# BLE112_Breakout_Board_v2_1_8mil.net
KiCad netlist of a schematic drawn in EAGLE
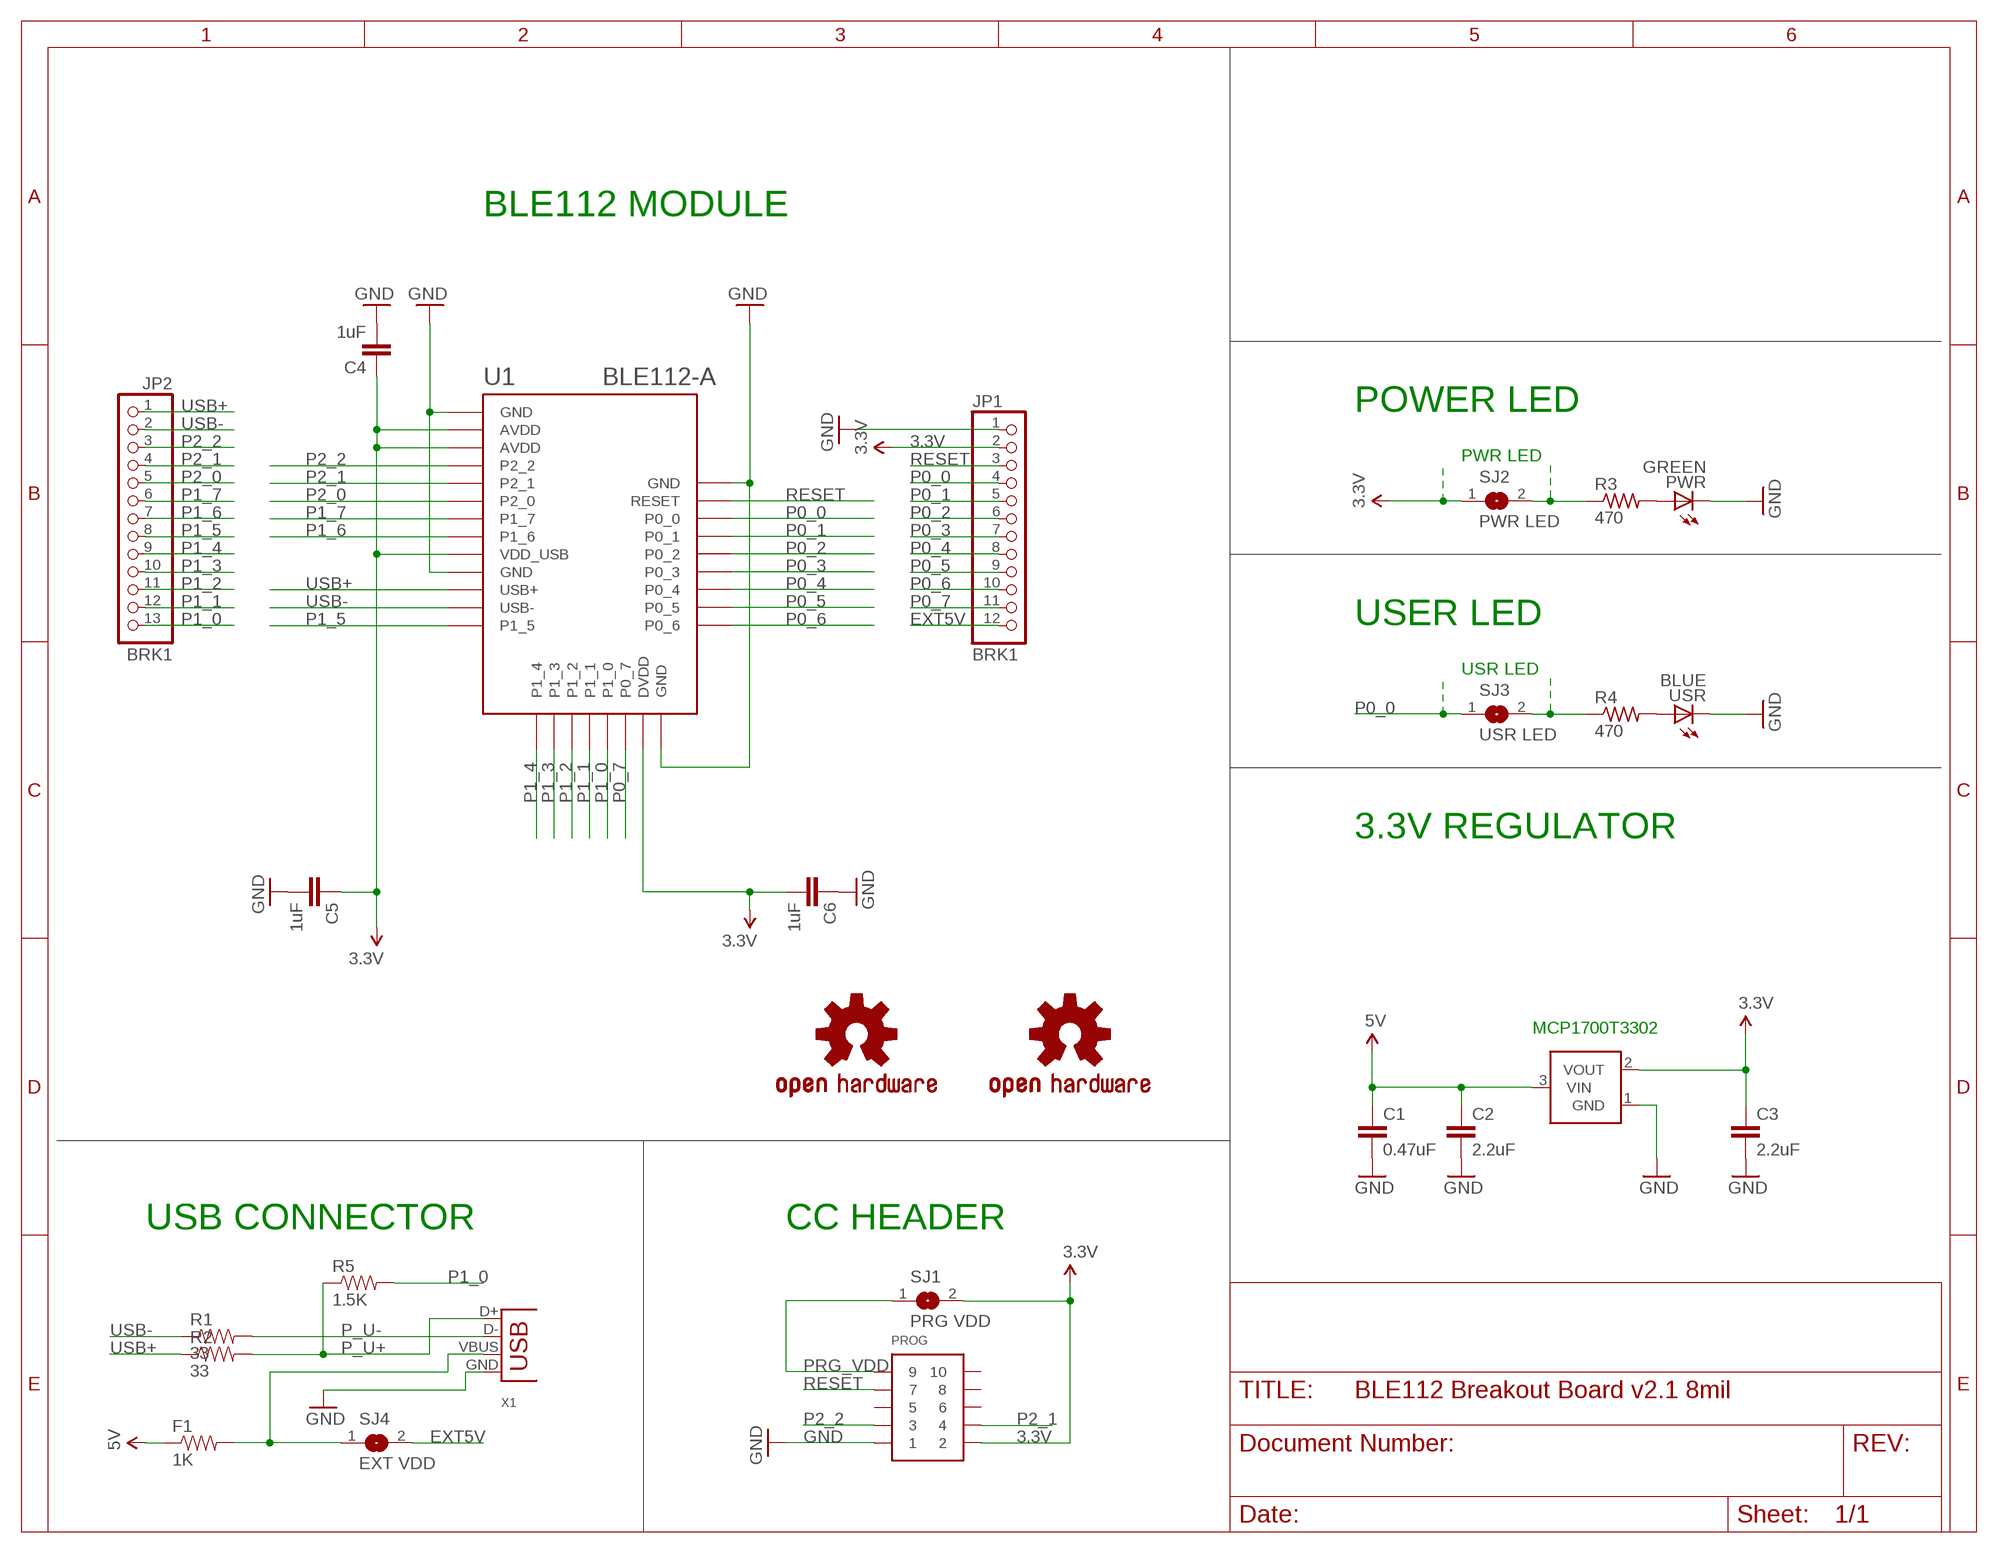
[diagram p0: schematic, sheet 1]

(export (version "E")
  (design (tool "Eeschema 10.0.6"))
  (components
    (comp (ref "C1")
      (value "0.47uF")
      (footprint "eagle-import:0603-CAP")
      (libsource (lib "eagle-import") (part "CAP0603-CAP"))
    )
    (comp (ref "C2")
      (value "2.2uF")
      (footprint "eagle-import:0603-CAP")
      (libsource (lib "eagle-import") (part "CAP0603-CAP"))
    )
    (comp (ref "C3")
      (value "2.2uF")
      (footprint "eagle-import:0603-CAP")
      (libsource (lib "eagle-import") (part "CAP0603-CAP"))
    )
    (comp (ref "C4")
      (value "1uF")
      (footprint "eagle-import:0603-CAP")
      (libsource (lib "eagle-import") (part "CAP0603-CAP"))
    )
    (comp (ref "C5")
      (value "1uF")
      (footprint "eagle-import:0603-CAP")
      (libsource (lib "eagle-import") (part "CAP0603-CAP"))
    )
    (comp (ref "C6")
      (value "1uF")
      (footprint "eagle-import:0603-CAP")
      (libsource (lib "eagle-import") (part "CAP0603-CAP"))
    )
    (comp (ref "F1")
      (value "1K")
      (footprint "eagle-import:0805")
      (libsource (lib "eagle-import") (part "RESISTOR0805-RES"))
    )
    (comp (ref "JP1")
      (value "BRK1")
      (footprint "eagle-import:1X12")
      (libsource (lib "eagle-import") (part "PINHD-1X12"))
    )
    (comp (ref "JP2")
      (value "BRK1")
      (footprint "eagle-import:1X13")
      (libsource (lib "eagle-import") (part "PINHD-1X13"))
    )
    (comp (ref "OSHW1")
      (value "OSHW-LOGOL")
      (footprint "eagle-import:OSHW-LOGO-L")
      (libsource (lib "eagle-import") (part "OSHW-LOGOL"))
    )
    (comp (ref "OSHW2")
      (value "OSHW-LOGOS")
      (footprint "eagle-import:OSHW-LOGO-S")
      (libsource (lib "eagle-import") (part "OSHW-LOGOS"))
    )
    (comp (ref "PROG")
      (value "CONN_5-2-FTSH-V")
      (footprint "eagle-import:FTSH-105-DV")
      (libsource (lib "eagle-import") (part "CONN_5-2-FTSH-V"))
    )
    (comp (ref "PWR")
      (value "GREEN")
      (footprint "eagle-import:CHIPLED_0805")
      (libsource (lib "eagle-import") (part "LEDCHIPLED_0805"))
    )
    (comp (ref "R1")
      (value "33")
      (footprint "eagle-import:0603-RES")
      (libsource (lib "eagle-import") (part "RESISTOR0603-RES"))
    )
    (comp (ref "R2")
      (value "33")
      (footprint "eagle-import:0603-RES")
      (libsource (lib "eagle-import") (part "RESISTOR0603-RES"))
    )
    (comp (ref "R3")
      (value "470")
      (footprint "eagle-import:R0603")
      (libsource (lib "eagle-import") (part "R-US_R0603"))
    )
    (comp (ref "R4")
      (value "470")
      (footprint "eagle-import:R0603")
      (libsource (lib "eagle-import") (part "R-US_R0603"))
    )
    (comp (ref "R5")
      (value "1.5K")
      (footprint "eagle-import:0603-RES")
      (libsource (lib "eagle-import") (part "RESISTOR0603-RES"))
    )
    (comp (ref "SJ1")
      (value "PRG VDD")
      (footprint "eagle-import:SJ")
      (libsource (lib "eagle-import") (part "SJ"))
    )
    (comp (ref "SJ2")
      (value "PWR LED")
      (footprint "eagle-import:SJ")
      (libsource (lib "eagle-import") (part "SJ"))
    )
    (comp (ref "SJ3")
      (value "USR LED")
      (footprint "eagle-import:SJ")
      (libsource (lib "eagle-import") (part "SJ"))
    )
    (comp (ref "SJ4")
      (value "EXT VDD")
      (footprint "eagle-import:SJ")
      (libsource (lib "eagle-import") (part "SJ"))
    )
    (comp (ref "U1")
      (value "BLE112-A")
      (footprint "eagle-import:BLE112-A")
      (libsource (lib "eagle-import") (part "BLE112-A-VISUAL"))
    )
    (comp (ref "U2")
      (value "MCP1700")
      (footprint "eagle-import:SOT23-3")
      (libsource (lib "eagle-import") (part "MCP1700"))
    )
    (comp (ref "USR")
      (value "BLUE")
      (footprint "eagle-import:CHIPLED_0805")
      (libsource (lib "eagle-import") (part "LEDCHIPLED_0805"))
    )
    (comp (ref "X1")
      (value "USB-MB-S")
      (footprint "eagle-import:USB-MB-S")
      (libsource (lib "eagle-import") (part "USB-MB-S"))
    )
  )
  (nets
    (net (code "1") (name "/EXT5V") (class "Default")
      (node (ref "JP1") (pin "12") (pinfunction "12_12") (pintype "passive"))
      (node (ref "SJ4") (pin "2") (pinfunction "2_2") (pintype "passive"))
    )
    (net (code "2") (name "/P0_0") (class "Default")
      (node (ref "JP1") (pin "4") (pinfunction "4_4") (pintype "passive"))
      (node (ref "SJ3") (pin "1") (pinfunction "1_1") (pintype "passive"))
      (node (ref "U1") (pin "P0_0") (pinfunction "P0_0_P0_0") (pintype "bidirectional"))
    )
    (net (code "3") (name "/P0_1") (class "Default")
      (node (ref "JP1") (pin "5") (pinfunction "5_5") (pintype "passive"))
      (node (ref "U1") (pin "P0_1") (pinfunction "P0_1_P0_1") (pintype "bidirectional"))
    )
    (net (code "4") (name "/P0_2") (class "Default")
      (node (ref "JP1") (pin "6") (pinfunction "6_6") (pintype "passive"))
      (node (ref "U1") (pin "P0_2") (pinfunction "P0_2_P0_2") (pintype "bidirectional"))
    )
    (net (code "5") (name "/P0_3") (class "Default")
      (node (ref "JP1") (pin "7") (pinfunction "7_7") (pintype "passive"))
      (node (ref "U1") (pin "P0_3") (pinfunction "P0_3_P0_3") (pintype "bidirectional"))
    )
    (net (code "6") (name "/P0_4") (class "Default")
      (node (ref "JP1") (pin "8") (pinfunction "8_8") (pintype "passive"))
      (node (ref "U1") (pin "P0_4") (pinfunction "P0_4_P0_4") (pintype "bidirectional"))
    )
    (net (code "7") (name "/P0_5") (class "Default")
      (node (ref "JP1") (pin "9") (pinfunction "9_9") (pintype "passive"))
      (node (ref "U1") (pin "P0_5") (pinfunction "P0_5_P0_5") (pintype "bidirectional"))
    )
    (net (code "8") (name "/P0_6") (class "Default")
      (node (ref "JP1") (pin "10") (pinfunction "10_10") (pintype "passive"))
      (node (ref "U1") (pin "P0_6") (pinfunction "P0_6_P0_6") (pintype "bidirectional"))
    )
    (net (code "9") (name "/P0_7") (class "Default")
      (node (ref "JP1") (pin "11") (pinfunction "11_11") (pintype "passive"))
      (node (ref "U1") (pin "P0_7") (pinfunction "P0_7_P0_7") (pintype "bidirectional"))
    )
    (net (code "10") (name "/P1_0") (class "Default")
      (node (ref "JP2") (pin "13") (pinfunction "13_13") (pintype "passive"))
      (node (ref "R5") (pin "2") (pinfunction "2_2") (pintype "passive"))
      (node (ref "U1") (pin "P1_0") (pinfunction "P1_0_P1_0") (pintype "bidirectional"))
    )
    (net (code "11") (name "/P1_1") (class "Default")
      (node (ref "JP2") (pin "12") (pinfunction "12_12") (pintype "passive"))
      (node (ref "U1") (pin "P1_1") (pinfunction "P1_1_P1_1") (pintype "bidirectional"))
    )
    (net (code "12") (name "/P1_2") (class "Default")
      (node (ref "JP2") (pin "11") (pinfunction "11_11") (pintype "passive"))
      (node (ref "U1") (pin "P1_2") (pinfunction "P1_2_P1_2") (pintype "bidirectional"))
    )
    (net (code "13") (name "/P1_3") (class "Default")
      (node (ref "JP2") (pin "10") (pinfunction "10_10") (pintype "passive"))
      (node (ref "U1") (pin "P1_3") (pinfunction "P1_3_P1_3") (pintype "bidirectional"))
    )
    (net (code "14") (name "/P1_4") (class "Default")
      (node (ref "JP2") (pin "9") (pinfunction "9_9") (pintype "passive"))
      (node (ref "U1") (pin "P1_4") (pinfunction "P1_4_P1_4") (pintype "bidirectional"))
    )
    (net (code "15") (name "/P1_5") (class "Default")
      (node (ref "JP2") (pin "8") (pinfunction "8_8") (pintype "passive"))
      (node (ref "U1") (pin "P1_5") (pinfunction "P1_5_P1_5") (pintype "bidirectional"))
    )
    (net (code "16") (name "/P1_6") (class "Default")
      (node (ref "JP2") (pin "7") (pinfunction "7_7") (pintype "passive"))
      (node (ref "U1") (pin "P1_6") (pinfunction "P1_6_P1_6") (pintype "bidirectional"))
    )
    (net (code "17") (name "/P1_7") (class "Default")
      (node (ref "JP2") (pin "6") (pinfunction "6_6") (pintype "passive"))
      (node (ref "U1") (pin "P1_7") (pinfunction "P1_7_P1_7") (pintype "bidirectional"))
    )
    (net (code "18") (name "/P2_0") (class "Default")
      (node (ref "JP2") (pin "5") (pinfunction "5_5") (pintype "passive"))
      (node (ref "U1") (pin "P2_0") (pinfunction "P2_0_P2_0") (pintype "bidirectional"))
    )
    (net (code "19") (name "/P2_1") (class "Default")
      (node (ref "JP2") (pin "4") (pinfunction "4_4") (pintype "passive"))
      (node (ref "PROG") (pin "4") (pinfunction "4_4") (pintype "bidirectional"))
      (node (ref "U1") (pin "P2_1") (pinfunction "P2_1_P2_1") (pintype "bidirectional"))
    )
    (net (code "20") (name "/P2_2") (class "Default")
      (node (ref "JP2") (pin "3") (pinfunction "3_3") (pintype "passive"))
      (node (ref "PROG") (pin "3") (pinfunction "3_3") (pintype "bidirectional"))
      (node (ref "U1") (pin "P2_2") (pinfunction "P2_2_P2_2") (pintype "bidirectional"))
    )
    (net (code "21") (name "/PRG_VDD") (class "Default")
      (node (ref "PROG") (pin "9") (pinfunction "9_9") (pintype "bidirectional"))
      (node (ref "SJ1") (pin "1") (pinfunction "1_1") (pintype "passive"))
    )
    (net (code "22") (name "/P_U+") (class "Default")
      (node (ref "R2") (pin "2") (pinfunction "2_2") (pintype "passive"))
      (node (ref "R5") (pin "1") (pinfunction "1_1") (pintype "passive"))
      (node (ref "X1") (pin "D+") (pinfunction "D+_D+") (pintype "bidirectional"))
    )
    (net (code "23") (name "/P_U-") (class "Default")
      (node (ref "R1") (pin "2") (pinfunction "2_2") (pintype "passive"))
      (node (ref "X1") (pin "D-") (pinfunction "D-_D-") (pintype "bidirectional"))
    )
    (net (code "24") (name "/RESET") (class "Default")
      (node (ref "JP1") (pin "3") (pinfunction "3_3") (pintype "passive"))
      (node (ref "PROG") (pin "7") (pinfunction "7_7") (pintype "bidirectional"))
      (node (ref "U1") (pin "RESET") (pinfunction "RESET_RESET") (pintype "input"))
    )
    (net (code "25") (name "/USB+") (class "Default")
      (node (ref "JP2") (pin "1") (pinfunction "1_1") (pintype "passive"))
      (node (ref "R2") (pin "1") (pinfunction "1_1") (pintype "passive"))
      (node (ref "U1") (pin "USB+") (pinfunction "USB+_USB+") (pintype "bidirectional"))
    )
    (net (code "26") (name "/USB-") (class "Default")
      (node (ref "JP2") (pin "2") (pinfunction "2_2") (pintype "passive"))
      (node (ref "R1") (pin "1") (pinfunction "1_1") (pintype "passive"))
      (node (ref "U1") (pin "USB-") (pinfunction "USB-_USB-") (pintype "bidirectional"))
    )
    (net (code "27") (name "3.3V") (class "Default")
      (node (ref "C3") (pin "1") (pinfunction "1_1") (pintype "passive"))
      (node (ref "C4") (pin "1") (pinfunction "1_1") (pintype "passive"))
      (node (ref "C5") (pin "1") (pinfunction "1_1") (pintype "passive"))
      (node (ref "C6") (pin "2") (pinfunction "2_2") (pintype "passive"))
      (node (ref "JP1") (pin "2") (pinfunction "2_2") (pintype "passive"))
      (node (ref "PROG") (pin "2") (pinfunction "2_2") (pintype "bidirectional"))
      (node (ref "SJ1") (pin "2") (pinfunction "2_2") (pintype "passive"))
      (node (ref "SJ2") (pin "1") (pinfunction "1_1") (pintype "passive"))
      (node (ref "U1") (pin "AVDD1") (pinfunction "AVDD_AVDD1") (pintype "power_in"))
      (node (ref "U1") (pin "AVDD2") (pinfunction "AVDD_AVDD2") (pintype "power_in"))
      (node (ref "U1") (pin "DVDD") (pinfunction "DVDD_DVDD") (pintype "power_in"))
      (node (ref "U1") (pin "VDD_USB") (pinfunction "VDD_USB_VDD_USB") (pintype "power_in"))
      (node (ref "U2") (pin "2") (pinfunction "VOUT_2") (pintype "power_in"))
    )
    (net (code "28") (name "5V") (class "Default")
      (node (ref "C1") (pin "1") (pinfunction "1_1") (pintype "passive"))
      (node (ref "C2") (pin "1") (pinfunction "1_1") (pintype "passive"))
      (node (ref "F1") (pin "1") (pinfunction "1_1") (pintype "passive"))
      (node (ref "U2") (pin "3") (pinfunction "VIN_3") (pintype "power_in"))
    )
    (net (code "29") (name "GND") (class "Default")
      (node (ref "C1") (pin "2") (pinfunction "2_2") (pintype "passive"))
      (node (ref "C2") (pin "2") (pinfunction "2_2") (pintype "passive"))
      (node (ref "C3") (pin "2") (pinfunction "2_2") (pintype "passive"))
      (node (ref "C4") (pin "2") (pinfunction "2_2") (pintype "passive"))
      (node (ref "C5") (pin "2") (pinfunction "2_2") (pintype "passive"))
      (node (ref "C6") (pin "1") (pinfunction "1_1") (pintype "passive"))
      (node (ref "JP1") (pin "1") (pinfunction "1_1") (pintype "passive"))
      (node (ref "PROG") (pin "1") (pinfunction "1_1") (pintype "bidirectional"))
      (node (ref "PWR") (pin "C") (pinfunction "C_C") (pintype "passive"))
      (node (ref "U1") (pin "GND1") (pinfunction "GND_GND1") (pintype "power_in"))
      (node (ref "U1") (pin "GND2") (pinfunction "GND_GND2") (pintype "power_in"))
      (node (ref "U1") (pin "GND3") (pinfunction "GND_GND3") (pintype "power_in"))
      (node (ref "U1") (pin "GND4") (pinfunction "GND_GND4") (pintype "power_in"))
      (node (ref "U2") (pin "1") (pinfunction "GND_1") (pintype "power_in"))
      (node (ref "USR") (pin "C") (pinfunction "C_C") (pintype "passive"))
      (node (ref "X1") (pin "GND") (pinfunction "GND_GND") (pintype "bidirectional"))
    )
    (net (code "30") (name "Net-(F1-Pad2)") (class "Default")
      (node (ref "F1") (pin "2") (pinfunction "2_2") (pintype "passive"))
      (node (ref "SJ4") (pin "1") (pinfunction "1_1") (pintype "passive"))
      (node (ref "X1") (pin "VBUS") (pinfunction "VBUS_VBUS") (pintype "bidirectional"))
    )
    (net (code "31") (name "Net-(PWR-PadA)") (class "Default")
      (node (ref "PWR") (pin "A") (pinfunction "A_A") (pintype "passive"))
      (node (ref "R3") (pin "2") (pinfunction "2_2") (pintype "passive"))
    )
    (net (code "32") (name "Net-(R3-Pad1)") (class "Default")
      (node (ref "R3") (pin "1") (pinfunction "1_1") (pintype "passive"))
      (node (ref "SJ2") (pin "2") (pinfunction "2_2") (pintype "passive"))
    )
    (net (code "33") (name "Net-(R4-Pad1)") (class "Default")
      (node (ref "R4") (pin "1") (pinfunction "1_1") (pintype "passive"))
      (node (ref "SJ3") (pin "2") (pinfunction "2_2") (pintype "passive"))
    )
    (net (code "34") (name "Net-(R4-Pad2)") (class "Default")
      (node (ref "R4") (pin "2") (pinfunction "2_2") (pintype "passive"))
      (node (ref "USR") (pin "A") (pinfunction "A_A") (pintype "passive"))
    )
    (net (code "35") (name "unconnected-(PROG-Pad5)") (class "Default")
      (node (ref "PROG") (pin "5") (pinfunction "5_5") (pintype "bidirectional"))
    )
    (net (code "36") (name "unconnected-(PROG-Pad6)") (class "Default")
      (node (ref "PROG") (pin "6") (pinfunction "6_6") (pintype "bidirectional"))
    )
    (net (code "37") (name "unconnected-(PROG-Pad8)") (class "Default")
      (node (ref "PROG") (pin "8") (pinfunction "8_8") (pintype "bidirectional"))
    )
    (net (code "38") (name "unconnected-(PROG-Pad10)") (class "Default")
      (node (ref "PROG") (pin "10") (pinfunction "10_10") (pintype "bidirectional"))
    )
  )
)
